# dc_q84_v2.net
KiCad netlist of a schematic drawn in EAGLE
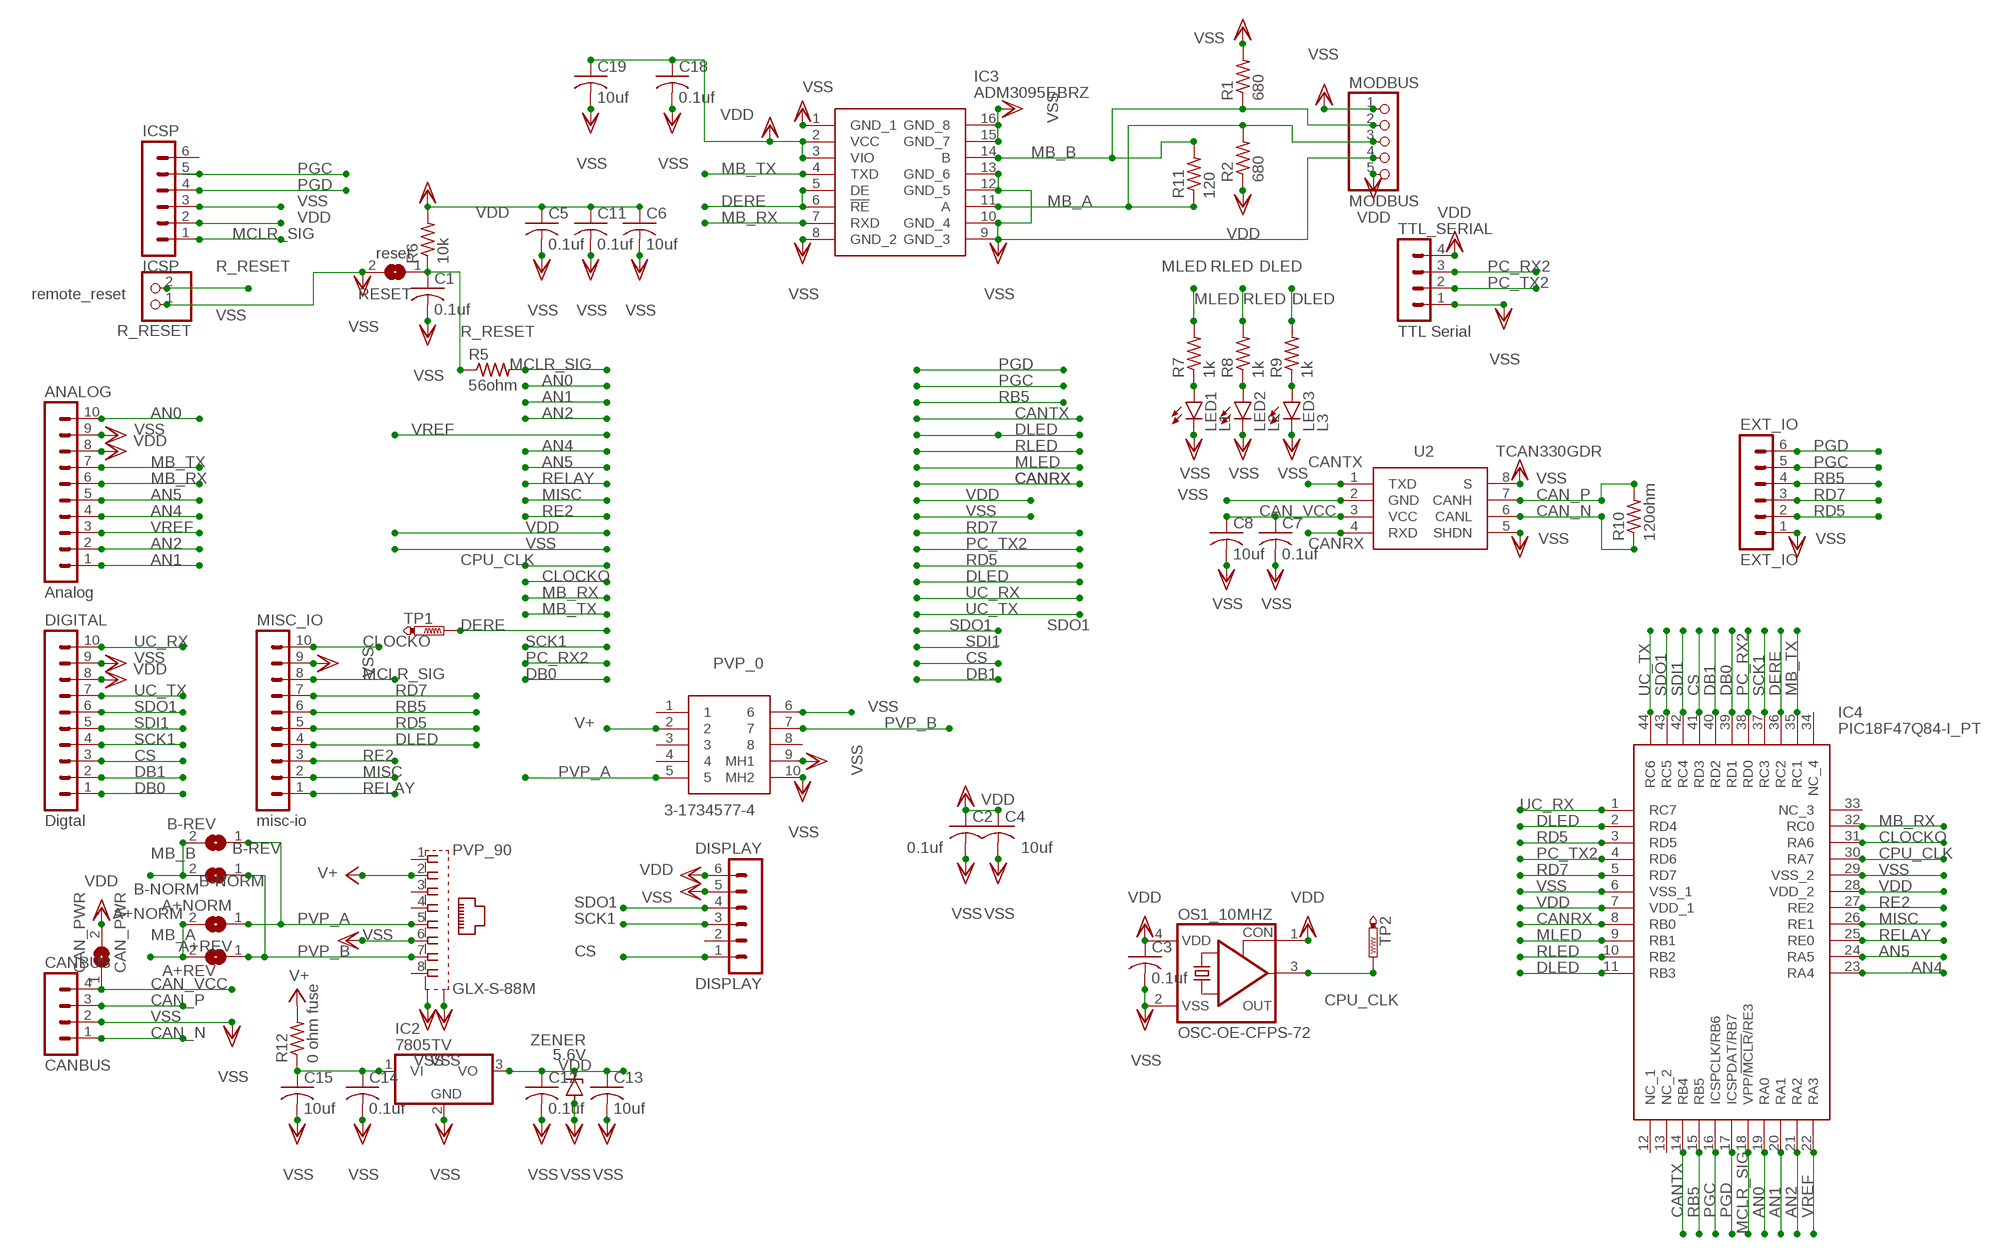
[diagram p0: schematic, sheet 1]

(export (version "E")
  (design (tool "Eeschema 10.0.6"))
  (components
    (comp (ref "A+NORM")
      (value "A+NORM")
      (footprint "eagle-import:SJ")
      (libsource (lib "eagle-import") (part "SJ"))
    )
    (comp (ref "A+REV")
      (value "A+REV")
      (footprint "eagle-import:SJ")
      (libsource (lib "eagle-import") (part "SJ"))
    )
    (comp (ref "ANALOG")
      (value "Analog")
      (footprint "eagle-import:MA10-1")
      (libsource (lib "eagle-import") (part "MA10-1"))
    )
    (comp (ref "B-NORM")
      (value "B-NORM")
      (footprint "eagle-import:SJ")
      (libsource (lib "eagle-import") (part "SJ"))
    )
    (comp (ref "B-REV")
      (value "B-REV")
      (footprint "eagle-import:SJ")
      (libsource (lib "eagle-import") (part "SJ"))
    )
    (comp (ref "C1")
      (value "0.1uf")
      (footprint "eagle-import:C0805")
      (libsource (lib "eagle-import") (part "C-USC0805"))
    )
    (comp (ref "C2")
      (value "0.1uf")
      (footprint "eagle-import:C0805")
      (libsource (lib "eagle-import") (part "C-USC0805"))
    )
    (comp (ref "C3")
      (value "0.1uf")
      (footprint "eagle-import:C0805")
      (libsource (lib "eagle-import") (part "C-USC0805"))
    )
    (comp (ref "C4")
      (value "10uf")
      (footprint "eagle-import:C0805")
      (libsource (lib "eagle-import") (part "C-USC0805"))
    )
    (comp (ref "C5")
      (value "0.1uf")
      (footprint "eagle-import:C0805")
      (libsource (lib "eagle-import") (part "C-USC0805"))
    )
    (comp (ref "C6")
      (value "10uf")
      (footprint "eagle-import:C0805")
      (libsource (lib "eagle-import") (part "C-USC0805"))
    )
    (comp (ref "C7")
      (value "0.1uf")
      (footprint "eagle-import:C0805")
      (libsource (lib "eagle-import") (part "C-USC0805"))
    )
    (comp (ref "C8")
      (value "10uf")
      (footprint "eagle-import:C0805")
      (libsource (lib "eagle-import") (part "C-USC0805"))
    )
    (comp (ref "C11")
      (value "0.1uf")
      (footprint "eagle-import:C0805")
      (libsource (lib "eagle-import") (part "C-USC0805"))
    )
    (comp (ref "C12")
      (value "0.1uf")
      (footprint "eagle-import:C0805")
      (libsource (lib "eagle-import") (part "C-USC0805"))
    )
    (comp (ref "C13")
      (value "10uf")
      (footprint "eagle-import:C0805")
      (libsource (lib "eagle-import") (part "C-USC0805"))
    )
    (comp (ref "C14")
      (value "0.1uf")
      (footprint "eagle-import:C0805")
      (libsource (lib "eagle-import") (part "C-USC0805"))
    )
    (comp (ref "C15")
      (value "10uf")
      (footprint "eagle-import:C0805")
      (libsource (lib "eagle-import") (part "C-USC0805"))
    )
    (comp (ref "C18")
      (value "0.1uf")
      (footprint "eagle-import:C0805")
      (libsource (lib "eagle-import") (part "C-USC0805"))
    )
    (comp (ref "C19")
      (value "10uf")
      (footprint "eagle-import:C0805")
      (libsource (lib "eagle-import") (part "C-USC0805"))
    )
    (comp (ref "CANBUS")
      (value "CANBUS")
      (footprint "eagle-import:MA04-1")
      (libsource (lib "eagle-import") (part "MA04-1"))
    )
    (comp (ref "CAN_PWR")
      (value "CAN_PWR")
      (footprint "eagle-import:SJ")
      (libsource (lib "eagle-import") (part "SJ"))
    )
    (comp (ref "DIGITAL")
      (value "Digtal")
      (footprint "eagle-import:MA10-1")
      (libsource (lib "eagle-import") (part "MA10-1"))
    )
    (comp (ref "DISPLAY")
      (value "DISPLAY")
      (footprint "eagle-import:MA06-1")
      (libsource (lib "eagle-import") (part "MA06-1"))
    )
    (comp (ref "EXT_IO")
      (value "EXT_IO")
      (footprint "eagle-import:MA06-1")
      (libsource (lib "eagle-import") (part "MA06-1"))
    )
    (comp (ref "IC2")
      (value "7805TV")
      (footprint "eagle-import:TO220V")
      (libsource (lib "eagle-import") (part "78TV05"))
    )
    (comp (ref "IC3")
      (value "ADM3095EBRZ")
      (footprint "eagle-import:SOIC127P600X175-16N")
      (fields (field (name "MOUSER_PART_NUMBER") "584-ADM3095EBRZ"))
      (libsource (lib "eagle-import") (part "ADM3095EBRZ"))
    )
    (comp (ref "IC4")
      (value "PIC18F47Q84-I_PT")
      (footprint "eagle-import:QFP80P1200X1200X120-44N")
      (fields
        (field (name "MANUFACTURER_PART_NUMBER") "PIC18F47Q84-I/PT")
        (field (name "MOUSER_PART_NUMBER") "579-PIC18F47Q84-I/PT")
      )
      (libsource (lib "eagle-import") (part "PIC18F47Q84-I_PT"))
    )
    (comp (ref "ICSP")
      (value "ICSP")
      (footprint "eagle-import:MA06-1")
      (libsource (lib "eagle-import") (part "MA06-1"))
    )
    (comp (ref "LED1")
      (value "L1")
      (footprint "eagle-import:CHIPLED_0805")
      (libsource (lib "eagle-import") (part "LEDCHIPLED_0805"))
    )
    (comp (ref "LED2")
      (value "L2")
      (footprint "eagle-import:CHIPLED_0805")
      (libsource (lib "eagle-import") (part "LEDCHIPLED_0805"))
    )
    (comp (ref "LED3")
      (value "L3")
      (footprint "eagle-import:CHIPLED_0805")
      (libsource (lib "eagle-import") (part "LEDCHIPLED_0805"))
    )
    (comp (ref "MISC_IO")
      (value "misc-io")
      (footprint "eagle-import:MA10-1")
      (libsource (lib "eagle-import") (part "MA10-1"))
    )
    (comp (ref "MODBUS")
      (value "MODBUS")
      (footprint "eagle-import:1X05")
      (libsource (lib "eagle-import") (part "PINHD-1X5"))
    )
    (comp (ref "OS1_10MHZ")
      (value "OSC-OE-CFPS-72")
      (footprint "eagle-import:7.2X5.2-4-PAD")
      (libsource (lib "eagle-import") (part "OSC-OE-CFPS-72"))
    )
    (comp (ref "PVP_0")
      (value "3-1734577-4")
      (footprint "eagle-import:317345774")
      (fields (field (name "MOUSER_PART_NUMBER") "571-3-1734577-4"))
      (libsource (lib "eagle-import") (part "3-1734577-4"))
    )
    (comp (ref "PVP_90")
      (value "GLX-S-88M")
      (footprint "eagle-import:GLX-S-88M")
      (libsource (lib "eagle-import") (part "GLX-S-88M"))
    )
    (comp (ref "R1")
      (value "680")
      (footprint "eagle-import:R0805")
      (libsource (lib "eagle-import") (part "R-US_R0805"))
    )
    (comp (ref "R2")
      (value "680")
      (footprint "eagle-import:R0805")
      (libsource (lib "eagle-import") (part "R-US_R0805"))
    )
    (comp (ref "R5")
      (value "56ohm")
      (footprint "eagle-import:R0805")
      (libsource (lib "eagle-import") (part "R-US_R0805"))
    )
    (comp (ref "R6")
      (value "10k")
      (footprint "eagle-import:R0805")
      (libsource (lib "eagle-import") (part "R-US_R0805"))
    )
    (comp (ref "R7")
      (value "1k")
      (footprint "eagle-import:R0805")
      (libsource (lib "eagle-import") (part "R-US_R0805"))
    )
    (comp (ref "R8")
      (value "1k")
      (footprint "eagle-import:R0805")
      (libsource (lib "eagle-import") (part "R-US_R0805"))
    )
    (comp (ref "R9")
      (value "1k")
      (footprint "eagle-import:R0805")
      (libsource (lib "eagle-import") (part "R-US_R0805"))
    )
    (comp (ref "R10")
      (value "120ohm")
      (footprint "eagle-import:R0805")
      (libsource (lib "eagle-import") (part "R-US_R0805"))
    )
    (comp (ref "R11")
      (value "120")
      (footprint "eagle-import:R0805")
      (libsource (lib "eagle-import") (part "R-US_R0805"))
    )
    (comp (ref "R12")
      (value "0 ohm fuse")
      (footprint "eagle-import:R1206")
      (libsource (lib "eagle-import") (part "R-US_R1206"))
    )
    (comp (ref "RESET")
      (value "reset")
      (footprint "eagle-import:SJ")
      (libsource (lib "eagle-import") (part "SJ"))
    )
    (comp (ref "R_RESET")
      (value "remote_reset")
      (footprint "eagle-import:1X02")
      (libsource (lib "eagle-import") (part "PINHD-1X2"))
    )
    (comp (ref "TP1")
      (value "PTR1PAD1-13")
      (footprint "eagle-import:P1-13")
      (libsource (lib "eagle-import") (part "PTR1PAD1-13"))
    )
    (comp (ref "TP2")
      (value "PTR1PAD1-13")
      (footprint "eagle-import:P1-13")
      (libsource (lib "eagle-import") (part "PTR1PAD1-13"))
    )
    (comp (ref "TTL_SERIAL")
      (value "TTL Serial")
      (footprint "eagle-import:MA04-1")
      (libsource (lib "eagle-import") (part "MA04-1"))
    )
    (comp (ref "U2")
      (value "TCAN330GDR")
      (footprint "eagle-import:SOIC127P600X175-8N")
      (fields (field (name "MOUSER_PART_NUMBER") "595-TCAN330GDR"))
      (libsource (lib "eagle-import") (part "TCAN330GDR"))
    )
    (comp (ref "ZENER")
      (value "5.6V")
      (footprint "eagle-import:SMB")
      (libsource (lib "eagle-import") (part "ZENER-DIODESMB"))
    )
  )
  (nets
    (net (code "1") (name "/AN0") (class "Default")
      (node (ref "ANALOG") (pin "10") (pinfunction "10_10") (pintype "passive"))
      (node (ref "IC4") (pin "19") (pinfunction "RA0_19") (pintype "bidirectional"))
    )
    (net (code "2") (name "/AN1") (class "Default")
      (node (ref "ANALOG") (pin "1") (pinfunction "1_1") (pintype "passive"))
      (node (ref "IC4") (pin "20") (pinfunction "RA1_20") (pintype "bidirectional"))
    )
    (net (code "3") (name "/AN2") (class "Default")
      (node (ref "ANALOG") (pin "2") (pinfunction "2_2") (pintype "passive"))
      (node (ref "IC4") (pin "21") (pinfunction "RA2_21") (pintype "bidirectional"))
    )
    (net (code "4") (name "/AN4") (class "Default")
      (node (ref "ANALOG") (pin "4") (pinfunction "4_4") (pintype "passive"))
      (node (ref "IC4") (pin "23") (pinfunction "RA4_23") (pintype "bidirectional"))
    )
    (net (code "5") (name "/AN5") (class "Default")
      (node (ref "ANALOG") (pin "5") (pinfunction "5_5") (pintype "passive"))
      (node (ref "IC4") (pin "24") (pinfunction "RA5_24") (pintype "bidirectional"))
    )
    (net (code "6") (name "/CANRX") (class "Default")
      (node (ref "IC4") (pin "8") (pinfunction "RB0_8") (pintype "bidirectional"))
      (node (ref "U2") (pin "4") (pinfunction "RXD_4") (pintype "output"))
    )
    (net (code "7") (name "/CANTX") (class "Default")
      (node (ref "IC4") (pin "14") (pinfunction "RB4_14") (pintype "bidirectional"))
      (node (ref "U2") (pin "1") (pinfunction "TXD_1") (pintype "input"))
    )
    (net (code "8") (name "/CAN_N") (class "Default")
      (node (ref "CANBUS") (pin "1") (pinfunction "1_1") (pintype "passive"))
      (node (ref "R10") (pin "1") (pinfunction "1_1") (pintype "passive"))
      (node (ref "U2") (pin "6") (pinfunction "CANL_6") (pintype "bidirectional"))
    )
    (net (code "9") (name "/CAN_P") (class "Default")
      (node (ref "CANBUS") (pin "3") (pinfunction "3_3") (pintype "passive"))
      (node (ref "R10") (pin "2") (pinfunction "2_2") (pintype "passive"))
      (node (ref "U2") (pin "7") (pinfunction "CANH_7") (pintype "bidirectional"))
    )
    (net (code "10") (name "/CAN_VCC") (class "Default")
      (node (ref "C7") (pin "1") (pinfunction "1_1") (pintype "passive"))
      (node (ref "C8") (pin "1") (pinfunction "1_1") (pintype "passive"))
      (node (ref "CANBUS") (pin "4") (pinfunction "4_4") (pintype "passive"))
      (node (ref "CAN_PWR") (pin "1") (pinfunction "1_1") (pintype "passive"))
      (node (ref "U2") (pin "3") (pinfunction "VCC_3") (pintype "power_in"))
    )
    (net (code "11") (name "/CLOCKO") (class "Default")
      (node (ref "IC4") (pin "31") (pinfunction "RA6_31") (pintype "bidirectional"))
      (node (ref "MISC_IO") (pin "10") (pinfunction "10_10") (pintype "passive"))
    )
    (net (code "12") (name "/CPU_CLK") (class "Default")
      (node (ref "IC4") (pin "30") (pinfunction "RA7_30") (pintype "bidirectional"))
      (node (ref "OS1_10MHZ") (pin "3") (pinfunction "OUT_3") (pintype "output"))
      (node (ref "TP2") (pin "TP") (pinfunction "TP_TP") (pintype "input"))
    )
    (net (code "13") (name "/CS") (class "Default")
      (node (ref "DIGITAL") (pin "3") (pinfunction "3_3") (pintype "passive"))
      (node (ref "DISPLAY") (pin "1") (pinfunction "1_1") (pintype "passive"))
      (node (ref "IC4") (pin "41") (pinfunction "RD3_41") (pintype "bidirectional"))
    )
    (net (code "14") (name "/DB0") (class "Default")
      (node (ref "DIGITAL") (pin "1") (pinfunction "1_1") (pintype "passive"))
      (node (ref "IC4") (pin "39") (pinfunction "RD1_39") (pintype "bidirectional"))
    )
    (net (code "15") (name "/DB1") (class "Default")
      (node (ref "DIGITAL") (pin "2") (pinfunction "2_2") (pintype "passive"))
      (node (ref "IC4") (pin "40") (pinfunction "RD2_40") (pintype "bidirectional"))
    )
    (net (code "16") (name "/DERE") (class "Default")
      (node (ref "IC3") (pin "5") (pinfunction "DE_5") (pintype "input"))
      (node (ref "IC3") (pin "6") (pinfunction "~{RE}_6") (pintype "input"))
      (node (ref "IC4") (pin "36") (pinfunction "RC2_36") (pintype "bidirectional"))
      (node (ref "TP1") (pin "TP") (pinfunction "TP_TP") (pintype "input"))
    )
    (net (code "17") (name "/DLED") (class "Default")
      (node (ref "IC4") (pin "11") (pinfunction "RB3_11") (pintype "bidirectional"))
      (node (ref "IC4") (pin "2") (pinfunction "RD4_2") (pintype "bidirectional"))
      (node (ref "MISC_IO") (pin "4") (pinfunction "4_4") (pintype "passive"))
      (node (ref "R9") (pin "2") (pinfunction "2_2") (pintype "passive"))
    )
    (net (code "18") (name "/MB_A") (class "Default")
      (node (ref "A+NORM") (pin "2") (pinfunction "2_2") (pintype "passive"))
      (node (ref "A+REV") (pin "2") (pinfunction "2_2") (pintype "passive"))
      (node (ref "IC3") (pin "11") (pinfunction "A_11") (pintype "bidirectional"))
      (node (ref "MODBUS") (pin "3") (pinfunction "3_3") (pintype "passive"))
      (node (ref "R11") (pin "1") (pinfunction "1_1") (pintype "passive"))
      (node (ref "R2") (pin "2") (pinfunction "2_2") (pintype "passive"))
    )
    (net (code "19") (name "/MB_B") (class "Default")
      (node (ref "B-NORM") (pin "2") (pinfunction "2_2") (pintype "passive"))
      (node (ref "B-REV") (pin "2") (pinfunction "2_2") (pintype "passive"))
      (node (ref "IC3") (pin "14") (pinfunction "B_14") (pintype "bidirectional"))
      (node (ref "MODBUS") (pin "2") (pinfunction "2_2") (pintype "passive"))
      (node (ref "R1") (pin "1") (pinfunction "1_1") (pintype "passive"))
      (node (ref "R11") (pin "2") (pinfunction "2_2") (pintype "passive"))
    )
    (net (code "20") (name "/MB_RX") (class "Default")
      (node (ref "ANALOG") (pin "6") (pinfunction "6_6") (pintype "passive"))
      (node (ref "IC3") (pin "7") (pinfunction "RXD_7") (pintype "output"))
      (node (ref "IC4") (pin "32") (pinfunction "RC0_32") (pintype "bidirectional"))
    )
    (net (code "21") (name "/MB_TX") (class "Default")
      (node (ref "ANALOG") (pin "7") (pinfunction "7_7") (pintype "passive"))
      (node (ref "IC3") (pin "4") (pinfunction "TXD_4") (pintype "input"))
      (node (ref "IC4") (pin "35") (pinfunction "RC1_35") (pintype "bidirectional"))
    )
    (net (code "22") (name "/MCLR_SIG") (class "Default")
      (node (ref "IC4") (pin "18") (pinfunction "VPP/~{MCLR}/RE3_18") (pintype "bidirectional"))
      (node (ref "ICSP") (pin "1") (pinfunction "1_1") (pintype "passive"))
      (node (ref "MISC_IO") (pin "8") (pinfunction "8_8") (pintype "passive"))
      (node (ref "R5") (pin "2") (pinfunction "2_2") (pintype "passive"))
    )
    (net (code "23") (name "/MISC") (class "Default")
      (node (ref "IC4") (pin "26") (pinfunction "RE1_26") (pintype "bidirectional"))
      (node (ref "MISC_IO") (pin "2") (pinfunction "2_2") (pintype "passive"))
    )
    (net (code "24") (name "/MLED") (class "Default")
      (node (ref "IC4") (pin "9") (pinfunction "RB1_9") (pintype "bidirectional"))
      (node (ref "R7") (pin "2") (pinfunction "2_2") (pintype "passive"))
    )
    (net (code "25") (name "/PC_RX2") (class "Default")
      (node (ref "IC4") (pin "38") (pinfunction "RD0_38") (pintype "bidirectional"))
      (node (ref "TTL_SERIAL") (pin "3") (pinfunction "3_3") (pintype "passive"))
    )
    (net (code "26") (name "/PC_TX2") (class "Default")
      (node (ref "IC4") (pin "4") (pinfunction "RD6_4") (pintype "bidirectional"))
      (node (ref "TTL_SERIAL") (pin "2") (pinfunction "2_2") (pintype "passive"))
    )
    (net (code "27") (name "/PGC") (class "Default")
      (node (ref "EXT_IO") (pin "5") (pinfunction "5_5") (pintype "passive"))
      (node (ref "IC4") (pin "16") (pinfunction "ICSPCLK/RB6_16") (pintype "bidirectional"))
      (node (ref "ICSP") (pin "5") (pinfunction "5_5") (pintype "passive"))
    )
    (net (code "28") (name "/PGD") (class "Default")
      (node (ref "EXT_IO") (pin "6") (pinfunction "6_6") (pintype "passive"))
      (node (ref "IC4") (pin "17") (pinfunction "ICSPDAT/RB7_17") (pintype "bidirectional"))
      (node (ref "ICSP") (pin "4") (pinfunction "4_4") (pintype "passive"))
    )
    (net (code "29") (name "/PVP_A") (class "Default")
      (node (ref "A+NORM") (pin "1") (pinfunction "1_1") (pintype "passive"))
      (node (ref "B-REV") (pin "1") (pinfunction "1_1") (pintype "passive"))
      (node (ref "PVP_0") (pin "5") (pinfunction "5_5") (pintype "bidirectional"))
      (node (ref "PVP_90") (pin "5") (pinfunction "5_5") (pintype "passive"))
    )
    (net (code "30") (name "/PVP_B") (class "Default")
      (node (ref "A+REV") (pin "1") (pinfunction "1_1") (pintype "passive"))
      (node (ref "B-NORM") (pin "1") (pinfunction "1_1") (pintype "passive"))
      (node (ref "PVP_0") (pin "7") (pinfunction "7_7") (pintype "bidirectional"))
      (node (ref "PVP_90") (pin "7") (pinfunction "7_7") (pintype "passive"))
    )
    (net (code "31") (name "/RB5") (class "Default")
      (node (ref "EXT_IO") (pin "4") (pinfunction "4_4") (pintype "passive"))
      (node (ref "IC4") (pin "15") (pinfunction "RB5_15") (pintype "bidirectional"))
      (node (ref "MISC_IO") (pin "6") (pinfunction "6_6") (pintype "passive"))
    )
    (net (code "32") (name "/RD5") (class "Default")
      (node (ref "EXT_IO") (pin "2") (pinfunction "2_2") (pintype "passive"))
      (node (ref "IC4") (pin "3") (pinfunction "RD5_3") (pintype "bidirectional"))
      (node (ref "MISC_IO") (pin "5") (pinfunction "5_5") (pintype "passive"))
    )
    (net (code "33") (name "/RD7") (class "Default")
      (node (ref "EXT_IO") (pin "3") (pinfunction "3_3") (pintype "passive"))
      (node (ref "IC4") (pin "5") (pinfunction "RD7_5") (pintype "bidirectional"))
      (node (ref "MISC_IO") (pin "7") (pinfunction "7_7") (pintype "passive"))
    )
    (net (code "34") (name "/RE2") (class "Default")
      (node (ref "IC4") (pin "27") (pinfunction "RE2_27") (pintype "bidirectional"))
      (node (ref "MISC_IO") (pin "3") (pinfunction "3_3") (pintype "passive"))
    )
    (net (code "35") (name "/RELAY") (class "Default")
      (node (ref "IC4") (pin "25") (pinfunction "RE0_25") (pintype "bidirectional"))
      (node (ref "MISC_IO") (pin "1") (pinfunction "1_1") (pintype "passive"))
    )
    (net (code "36") (name "/RLED") (class "Default")
      (node (ref "IC4") (pin "10") (pinfunction "RB2_10") (pintype "bidirectional"))
      (node (ref "R8") (pin "2") (pinfunction "2_2") (pintype "passive"))
    )
    (net (code "37") (name "/R_RESET") (class "Default")
      (node (ref "C1") (pin "1") (pinfunction "1_1") (pintype "passive"))
      (node (ref "R5") (pin "1") (pinfunction "1_1") (pintype "passive"))
      (node (ref "R6") (pin "1") (pinfunction "1_1") (pintype "passive"))
      (node (ref "RESET") (pin "1") (pinfunction "1_1") (pintype "passive"))
      (node (ref "R_RESET") (pin "2") (pinfunction "2_2") (pintype "passive"))
    )
    (net (code "38") (name "/SCK1") (class "Default")
      (node (ref "DIGITAL") (pin "4") (pinfunction "4_4") (pintype "passive"))
      (node (ref "DISPLAY") (pin "3") (pinfunction "3_3") (pintype "passive"))
      (node (ref "IC4") (pin "37") (pinfunction "RC3_37") (pintype "bidirectional"))
    )
    (net (code "39") (name "/SDI1") (class "Default")
      (node (ref "DIGITAL") (pin "5") (pinfunction "5_5") (pintype "passive"))
      (node (ref "IC4") (pin "42") (pinfunction "RC4_42") (pintype "bidirectional"))
    )
    (net (code "40") (name "/SDO1") (class "Default")
      (node (ref "DIGITAL") (pin "6") (pinfunction "6_6") (pintype "passive"))
      (node (ref "DISPLAY") (pin "4") (pinfunction "4_4") (pintype "passive"))
      (node (ref "IC4") (pin "43") (pinfunction "RC5_43") (pintype "bidirectional"))
    )
    (net (code "41") (name "/UC_RX") (class "Default")
      (node (ref "DIGITAL") (pin "10") (pinfunction "10_10") (pintype "passive"))
      (node (ref "IC4") (pin "1") (pinfunction "RC7_1") (pintype "bidirectional"))
    )
    (net (code "42") (name "/UC_TX") (class "Default")
      (node (ref "DIGITAL") (pin "7") (pinfunction "7_7") (pintype "passive"))
      (node (ref "IC4") (pin "44") (pinfunction "RC6_44") (pintype "bidirectional"))
    )
    (net (code "43") (name "/VREF") (class "Default")
      (node (ref "ANALOG") (pin "3") (pinfunction "3_3") (pintype "passive"))
      (node (ref "IC4") (pin "22") (pinfunction "RA3_22") (pintype "bidirectional"))
    )
    (net (code "44") (name "Net-(IC2-VI)") (class "Default")
      (node (ref "C14") (pin "1") (pinfunction "1_1") (pintype "passive"))
      (node (ref "C15") (pin "1") (pinfunction "1_1") (pintype "passive"))
      (node (ref "IC2") (pin "1") (pinfunction "VI_1") (pintype "input"))
      (node (ref "R12") (pin "1") (pinfunction "1_1") (pintype "passive"))
    )
    (net (code "45") (name "Net-(LED1-PadA)") (class "Default")
      (node (ref "LED1") (pin "A") (pinfunction "A_A") (pintype "passive"))
      (node (ref "R7") (pin "1") (pinfunction "1_1") (pintype "passive"))
    )
    (net (code "46") (name "Net-(LED2-PadA)") (class "Default")
      (node (ref "LED2") (pin "A") (pinfunction "A_A") (pintype "passive"))
      (node (ref "R8") (pin "1") (pinfunction "1_1") (pintype "passive"))
    )
    (net (code "47") (name "Net-(LED3-PadA)") (class "Default")
      (node (ref "LED3") (pin "A") (pinfunction "A_A") (pintype "passive"))
      (node (ref "R9") (pin "1") (pinfunction "1_1") (pintype "passive"))
    )
    (net (code "48") (name "V+") (class "Default")
      (node (ref "PVP_0") (pin "2") (pinfunction "2_2") (pintype "bidirectional"))
      (node (ref "PVP_90") (pin "2") (pinfunction "2_2") (pintype "passive"))
      (node (ref "R12") (pin "2") (pinfunction "2_2") (pintype "passive"))
    )
    (net (code "49") (name "VDD") (class "Default")
      (node (ref "ANALOG") (pin "8") (pinfunction "8_8") (pintype "passive"))
      (node (ref "C11") (pin "1") (pinfunction "1_1") (pintype "passive"))
      (node (ref "C12") (pin "1") (pinfunction "1_1") (pintype "passive"))
      (node (ref "C13") (pin "1") (pinfunction "1_1") (pintype "passive"))
      (node (ref "C18") (pin "1") (pinfunction "1_1") (pintype "passive"))
      (node (ref "C19") (pin "1") (pinfunction "1_1") (pintype "passive"))
      (node (ref "C2") (pin "1") (pinfunction "1_1") (pintype "passive"))
      (node (ref "C3") (pin "1") (pinfunction "1_1") (pintype "passive"))
      (node (ref "C4") (pin "1") (pinfunction "1_1") (pintype "passive"))
      (node (ref "C5") (pin "1") (pinfunction "1_1") (pintype "passive"))
      (node (ref "C6") (pin "1") (pinfunction "1_1") (pintype "passive"))
      (node (ref "CAN_PWR") (pin "2") (pinfunction "2_2") (pintype "passive"))
      (node (ref "DIGITAL") (pin "8") (pinfunction "8_8") (pintype "passive"))
      (node (ref "DISPLAY") (pin "6") (pinfunction "6_6") (pintype "passive"))
      (node (ref "IC2") (pin "3") (pinfunction "VO_3") (pintype "passive"))
      (node (ref "IC3") (pin "2") (pinfunction "VCC_2") (pintype "power_in"))
      (node (ref "IC3") (pin "3") (pinfunction "VIO_3") (pintype "power_in"))
      (node (ref "IC4") (pin "28") (pinfunction "VDD_2_28") (pintype "bidirectional"))
      (node (ref "IC4") (pin "7") (pinfunction "VDD_1_7") (pintype "bidirectional"))
      (node (ref "ICSP") (pin "2") (pinfunction "2_2") (pintype "passive"))
      (node (ref "MODBUS") (pin "5") (pinfunction "5_5") (pintype "passive"))
      (node (ref "OS1_10MHZ") (pin "1") (pinfunction "CON_1") (pintype "input"))
      (node (ref "OS1_10MHZ") (pin "4") (pinfunction "VDD_4") (pintype "power_in"))
      (node (ref "R2") (pin "1") (pinfunction "1_1") (pintype "passive"))
      (node (ref "R6") (pin "2") (pinfunction "2_2") (pintype "passive"))
      (node (ref "TTL_SERIAL") (pin "4") (pinfunction "4_4") (pintype "passive"))
      (node (ref "ZENER") (pin "C") (pinfunction "C_C") (pintype "passive"))
    )
    (net (code "50") (name "VSS") (class "Default")
      (node (ref "ANALOG") (pin "9") (pinfunction "9_9") (pintype "passive"))
      (node (ref "C1") (pin "2") (pinfunction "2_2") (pintype "passive"))
      (node (ref "C11") (pin "2") (pinfunction "2_2") (pintype "passive"))
      (node (ref "C12") (pin "2") (pinfunction "2_2") (pintype "passive"))
      (node (ref "C13") (pin "2") (pinfunction "2_2") (pintype "passive"))
      (node (ref "C14") (pin "2") (pinfunction "2_2") (pintype "passive"))
      (node (ref "C15") (pin "2") (pinfunction "2_2") (pintype "passive"))
      (node (ref "C18") (pin "2") (pinfunction "2_2") (pintype "passive"))
      (node (ref "C19") (pin "2") (pinfunction "2_2") (pintype "passive"))
      (node (ref "C2") (pin "2") (pinfunction "2_2") (pintype "passive"))
      (node (ref "C3") (pin "2") (pinfunction "2_2") (pintype "passive"))
      (node (ref "C4") (pin "2") (pinfunction "2_2") (pintype "passive"))
      (node (ref "C5") (pin "2") (pinfunction "2_2") (pintype "passive"))
      (node (ref "C6") (pin "2") (pinfunction "2_2") (pintype "passive"))
      (node (ref "C7") (pin "2") (pinfunction "2_2") (pintype "passive"))
      (node (ref "C8") (pin "2") (pinfunction "2_2") (pintype "passive"))
      (node (ref "CANBUS") (pin "2") (pinfunction "2_2") (pintype "passive"))
      (node (ref "DIGITAL") (pin "9") (pinfunction "9_9") (pintype "passive"))
      (node (ref "DISPLAY") (pin "5") (pinfunction "5_5") (pintype "passive"))
      (node (ref "EXT_IO") (pin "1") (pinfunction "1_1") (pintype "passive"))
      (node (ref "IC2") (pin "2") (pinfunction "GND_2") (pintype "passive"))
      (node (ref "IC3") (pin "1") (pinfunction "GND_1_1") (pintype "power_in"))
      (node (ref "IC3") (pin "10") (pinfunction "GND_4_10") (pintype "power_in"))
      (node (ref "IC3") (pin "12") (pinfunction "GND_5_12") (pintype "power_in"))
      (node (ref "IC3") (pin "13") (pinfunction "GND_6_13") (pintype "power_in"))
      (node (ref "IC3") (pin "15") (pinfunction "GND_7_15") (pintype "power_in"))
      (node (ref "IC3") (pin "16") (pinfunction "GND_8_16") (pintype "power_in"))
      (node (ref "IC3") (pin "8") (pinfunction "GND_2_8") (pintype "power_in"))
      (node (ref "IC3") (pin "9") (pinfunction "GND_3_9") (pintype "power_in"))
      (node (ref "IC4") (pin "29") (pinfunction "VSS_2_29") (pintype "bidirectional"))
      (node (ref "IC4") (pin "6") (pinfunction "VSS_1_6") (pintype "bidirectional"))
      (node (ref "ICSP") (pin "3") (pinfunction "3_3") (pintype "passive"))
      (node (ref "LED1") (pin "C") (pinfunction "C_C") (pintype "passive"))
      (node (ref "LED2") (pin "C") (pinfunction "C_C") (pintype "passive"))
      (node (ref "LED3") (pin "C") (pinfunction "C_C") (pintype "passive"))
      (node (ref "MISC_IO") (pin "9") (pinfunction "9_9") (pintype "passive"))
      (node (ref "MODBUS") (pin "1") (pinfunction "1_1") (pintype "passive"))
      (node (ref "MODBUS") (pin "4") (pinfunction "4_4") (pintype "passive"))
      (node (ref "OS1_10MHZ") (pin "2") (pinfunction "VSS_2") (pintype "power_in"))
      (node (ref "PVP_0") (pin "10") (pinfunction "MH2_10") (pintype "bidirectional"))
      (node (ref "PVP_0") (pin "6") (pinfunction "6_6") (pintype "bidirectional"))
      (node (ref "PVP_0") (pin "9") (pinfunction "MH1_9") (pintype "bidirectional"))
      (node (ref "PVP_90") (pin "6") (pinfunction "6_6") (pintype "passive"))
      (node (ref "PVP_90") (pin "S1") (pinfunction "S1_S1") (pintype "passive"))
      (node (ref "PVP_90") (pin "S2") (pinfunction "S2_S2") (pintype "passive"))
      (node (ref "R1") (pin "2") (pinfunction "2_2") (pintype "passive"))
      (node (ref "RESET") (pin "2") (pinfunction "2_2") (pintype "passive"))
      (node (ref "R_RESET") (pin "1") (pinfunction "1_1") (pintype "passive"))
      (node (ref "TTL_SERIAL") (pin "1") (pinfunction "1_1") (pintype "passive"))
      (node (ref "U2") (pin "2") (pinfunction "GND_2") (pintype "power_in"))
      (node (ref "U2") (pin "5") (pinfunction "SHDN_5") (pintype "bidirectional"))
      (node (ref "U2") (pin "8") (pinfunction "S_8") (pintype "bidirectional"))
      (node (ref "ZENER") (pin "A") (pinfunction "A_A") (pintype "passive"))
    )
    (net (code "51") (name "unconnected-(DISPLAY-Pad2)") (class "Default")
      (node (ref "DISPLAY") (pin "2") (pinfunction "2_2") (pintype "passive"))
    )
    (net (code "52") (name "unconnected-(IC4-NC_1-Pad12)") (class "Default")
      (node (ref "IC4") (pin "12") (pinfunction "NC_1_12") (pintype "bidirectional"))
    )
    (net (code "53") (name "unconnected-(IC4-NC_2-Pad13)") (class "Default")
      (node (ref "IC4") (pin "13") (pinfunction "NC_2_13") (pintype "bidirectional"))
    )
    (net (code "54") (name "unconnected-(IC4-NC_3-Pad33)") (class "Default")
      (node (ref "IC4") (pin "33") (pinfunction "NC_3_33") (pintype "bidirectional"))
    )
    (net (code "55") (name "unconnected-(IC4-NC_4-Pad34)") (class "Default")
      (node (ref "IC4") (pin "34") (pinfunction "NC_4_34") (pintype "bidirectional"))
    )
    (net (code "56") (name "unconnected-(ICSP-Pad6)") (class "Default")
      (node (ref "ICSP") (pin "6") (pinfunction "6_6") (pintype "passive"))
    )
    (net (code "57") (name "unconnected-(PVP_0-Pad1)") (class "Default")
      (node (ref "PVP_0") (pin "1") (pinfunction "1_1") (pintype "bidirectional"))
    )
    (net (code "58") (name "unconnected-(PVP_0-Pad3)") (class "Default")
      (node (ref "PVP_0") (pin "3") (pinfunction "3_3") (pintype "bidirectional"))
    )
    (net (code "59") (name "unconnected-(PVP_0-Pad4)") (class "Default")
      (node (ref "PVP_0") (pin "4") (pinfunction "4_4") (pintype "bidirectional"))
    )
    (net (code "60") (name "unconnected-(PVP_0-Pad8)") (class "Default")
      (node (ref "PVP_0") (pin "8") (pinfunction "8_8") (pintype "bidirectional"))
    )
    (net (code "61") (name "unconnected-(PVP_90-Pad1)") (class "Default")
      (node (ref "PVP_90") (pin "1") (pinfunction "1_1") (pintype "passive"))
    )
    (net (code "62") (name "unconnected-(PVP_90-Pad3)") (class "Default")
      (node (ref "PVP_90") (pin "3") (pinfunction "3_3") (pintype "passive"))
    )
    (net (code "63") (name "unconnected-(PVP_90-Pad4)") (class "Default")
      (node (ref "PVP_90") (pin "4") (pinfunction "4_4") (pintype "passive"))
    )
    (net (code "64") (name "unconnected-(PVP_90-Pad8)") (class "Default")
      (node (ref "PVP_90") (pin "8") (pinfunction "8_8") (pintype "passive"))
    )
  )
)
